# Microprocessor.net
KiCad netlist of a schematic drawn in Altium Designer
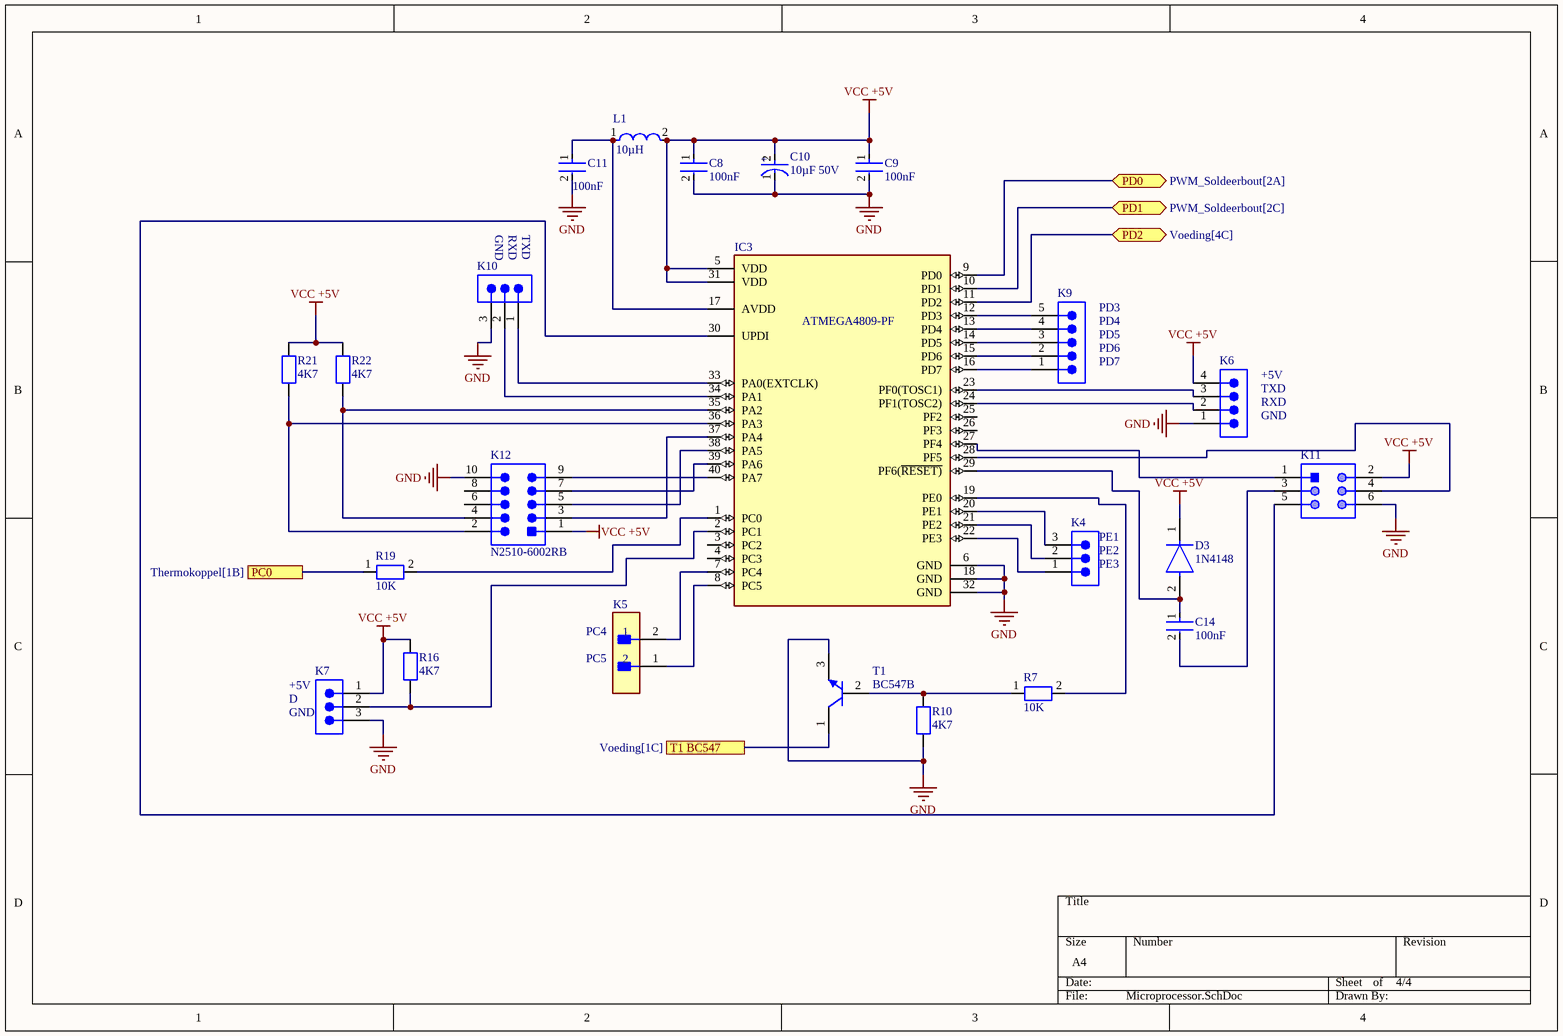
[diagram p0: Microprocessor.SchDoc]

(export (version "E")
  (design (tool "Eeschema 10.0.6"))
  (components
    (comp (ref "C8")
      (value "100nF")
      (footprint "FP-C0805C-DN-IPC_A")
      (description "Chip Multilayer Ceramic Capacitors for Automotive, 0805, 0.10uF, X7R, 15%, 10%, 50V, Grade 1")
      (fields (field (name "TOLERANCE") "10%"))
      (libsource (lib "soldeerstation") (part "cap 50V 100nF"))
    )
    (comp (ref "C9")
      (value "100nF")
      (footprint "FP-C0805C-DN-IPC_A")
      (description "Chip Multilayer Ceramic Capacitors for Automotive, 0805, 0.10uF, X7R, 15%, 10%, 50V, Grade 1")
      (fields (field (name "TOLERANCE") "10%"))
      (libsource (lib "soldeerstation") (part "cap 50V 100nF"))
    )
    (comp (ref "C10")
      (value "10µF 50V")
      (footprint "cap 10µF 50V")
      (description "Aluminum Electrolytic Capacitors (Radial Lead Type) 10uF ±20% 50V")
      (fields (field (name "TOLERANCE") "20%") (field (name "VOLTAGE") "50V"))
      (libsource (lib "soldeerstation") (part "10µF 50V"))
    )
    (comp (ref "C11")
      (value "100nF")
      (footprint "FP-C0805C-DN-IPC_A")
      (description "Chip Multilayer Ceramic Capacitors for Automotive, 0805, 0.10uF, X7R, 15%, 10%, 50V, Grade 1")
      (fields (field (name "TOLERANCE") "10%"))
      (libsource (lib "soldeerstation") (part "cap 50V 100nF"))
    )
    (comp (ref "C14")
      (value "100nF")
      (footprint "FP-C0805C-DN-IPC_A")
      (description "Chip Multilayer Ceramic Capacitors for Automotive, 0805, 0.10uF, X7R, 15%, 10%, 50V, Grade 1")
      (fields (field (name "TOLERANCE") "10%"))
      (libsource (lib "soldeerstation") (part "cap 50V 100nF"))
    )
    (comp (ref "D3")
      (value "1N4148")
      (footprint "1N4148")
      (description "DIODE GEN PURP 100V 200MA DO35")
      (fields (field (name "VOLTAGE") "100V"))
      (libsource (lib "soldeerstation") (part "1N4148"))
    )
    (comp (ref "IC3")
      (value "ATMEGA4809-PF")
      (footprint "ATMEGCPU")
      (description "IC MCU 8BIT 48KB FLASH 40DIP")
      (libsource (lib "soldeerstation") (part "ATMEGA4809-PF"))
    )
    (comp (ref "K4")
      (value "~")
      (footprint "Pinheader (1rij-3pin)")
      (description "0.025\" SQ Post Header, Through-hole, Vertical, -55 to 105 degC, 2.54 mm Pitch, 3-Pin, Male, RoHS")
      (fields (field (name "PARTNUMBER") "TSW-103-07-T-S") (field (name "MANUFACTURER") "Samtec"))
      (libsource (lib "soldeerstation") (part "Pinheader (1rij-3pin)"))
    )
    (comp (ref "K5")
      (value "~")
      (footprint "Pinheader (1rij-2pin)")
      (description "CONN HEADER VERT 2POS 2.54MM")
      (fields
        (field (name "OCTOPART") "https://octopart.com/m20-9990246-harwin-2590635")
        (field (name "MANUFACTURER") "Harwin")
      )
      (libsource (lib "soldeerstation") (part "Pinheader (1rij-2pin)"))
    )
    (comp (ref "K6")
      (value "~")
      (footprint "Pinheader (1rij-4pin)")
      (description "0.025\" SQ Post Header, Through-hole, Vertical, -55 to 125 degC, 2.54 mm Pitch, 4-Pin, Male, RoHS")
      (fields (field (name "PARTNUMBER") "TSW-104-08-L-S") (field (name "MANUFACTURER") "Samtec"))
      (libsource (lib "soldeerstation") (part "Pinheader (1rij - 4pin)"))
    )
    (comp (ref "K7")
      (value "~")
      (footprint "Pinheader (1rij-3pin)")
      (description "0.025\" SQ Post Header, Through-hole, Vertical, -55 to 105 degC, 2.54 mm Pitch, 3-Pin, Male, RoHS")
      (fields (field (name "PARTNUMBER") "TSW-103-07-T-S") (field (name "MANUFACTURER") "Samtec"))
      (libsource (lib "soldeerstation") (part "Pinheader (1rij-3pin)"))
    )
    (comp (ref "K9")
      (value "~")
      (footprint "Pinheader (1rij-5pin)")
      (description "0.025\" SQ Post Header, Through-hole, Vertical, -55 to 125 degC, 2.54 mm Pitch, 5-Pin, Male, RoHS")
      (fields (field (name "PARTNUMBER") "TSW-105-05-F-S") (field (name "MANUFACTURER") "Samtec"))
      (libsource (lib "soldeerstation") (part "Pinheader (1rij-5pin)"))
    )
    (comp (ref "K10")
      (value "~")
      (footprint "Pinheader (1rij-3pin)")
      (description "0.025\" SQ Post Header, Through-hole, Vertical, -55 to 105 degC, 2.54 mm Pitch, 3-Pin, Male, RoHS")
      (fields (field (name "PARTNUMBER") "TSW-103-07-T-S") (field (name "MANUFACTURER") "Samtec"))
      (libsource (lib "soldeerstation") (part "Pinheader (1rij-3pin)"))
    )
    (comp (ref "K11")
      (value "~")
      (footprint "Pinheader (2rij-6pin)")
      (description "THT Vertical Pin Header WR-PHD, Pitch 2.54 mm, Dual Row, 6 pins")
      (fields
        (field (name "MANUFACTURER") "Wurth Elektronik")
        (field (name "PART NUMBER") "61300621121")
        (field (name "PUBLISHER") "WurthElektronik")
      )
      (libsource (lib "soldeerstation") (part "Pinheader (2rij-6pin)"))
    )
    (comp (ref "K12")
      (value "N2510-6002RB")
      (footprint "boxheader")
      (fields (field (name "PARTNUMBER") "N2510") (field (name "MANUFACTURER") "3M"))
      (libsource (lib "soldeerstation") (part "boxheader"))
    )
    (comp (ref "L1")
      (value "10µH")
      (footprint "Spoel L1 10µH,130mA")
      (description "IR-2 10 10% B08")
      (fields (field (name "TOLERANCE") "10%") (field (name "OBSOLETE PART") "true"))
      (libsource (lib "soldeerstation") (part "Spoel L1 10µH,130mA"))
    )
    (comp (ref "R7")
      (value "10K")
      (footprint "Weerstand 1M ohm")
      (description "RES Thick Film, 10kΩ, 1%, 0.125W, 100ppm/°C, 0805")
      (fields (field (name "TOLERANCE") "1%"))
      (libsource (lib "soldeerstation") (part "Weerstand 10K ohm"))
    )
    (comp (ref "R10")
      (value "4K7")
      (footprint "Weerstand 1M ohm")
      (fields (field (name "MANUFACTURER") "Vishay Dale") (field (name "PART NUMBER") "CRCW08054K70JNEB"))
      (libsource (lib "soldeerstation") (part "Weerstand 4K7 ohm"))
    )
    (comp (ref "R16")
      (value "4K7")
      (footprint "Weerstand 1M ohm")
      (fields (field (name "MANUFACTURER") "Vishay Dale") (field (name "PART NUMBER") "CRCW08054K70JNEB"))
      (libsource (lib "soldeerstation") (part "Weerstand 4K7 ohm"))
    )
    (comp (ref "R19")
      (value "10K")
      (footprint "Weerstand 1M ohm")
      (description "RES Thick Film, 10kΩ, 1%, 0.125W, 100ppm/°C, 0805")
      (fields (field (name "TOLERANCE") "1%"))
      (libsource (lib "soldeerstation") (part "Weerstand 10K ohm"))
    )
    (comp (ref "R21")
      (value "4K7")
      (footprint "Weerstand 1M ohm")
      (fields (field (name "MANUFACTURER") "Vishay Dale") (field (name "PART NUMBER") "CRCW08054K70JNEB"))
      (libsource (lib "soldeerstation") (part "Weerstand 4K7 ohm"))
    )
    (comp (ref "R22")
      (value "4K7")
      (footprint "Weerstand 1M ohm")
      (fields (field (name "MANUFACTURER") "Vishay Dale") (field (name "PART NUMBER") "CRCW08054K70JNEB"))
      (libsource (lib "soldeerstation") (part "Weerstand 4K7 ohm"))
    )
    (comp (ref "T1")
      (value "BC547B")
      (footprint "sot23")
      (description "Amplifier Transistor, NPN Silicon, 3-Pin TO-92, Bulk Box")
      (fields (field (name "MANUFACTURER") "On Semiconductor"))
      (libsource (lib "soldeerstation") (part "sot23 (bc547)"))
    )
  )
  (nets
    (net (code "1") (name "/PC0") (class "Default")
      (node (ref "R19") (pin "1") (pinfunction "1_1") (pintype "passive"))
    )
    (net (code "2") (name "/PD0") (class "Default")
      (node (ref "IC3") (pin "9") (pinfunction "PD0_9") (pintype "bidirectional"))
    )
    (net (code "3") (name "/PD1") (class "Default")
      (node (ref "IC3") (pin "10") (pinfunction "PD1_10") (pintype "bidirectional"))
    )
    (net (code "4") (name "/PD2") (class "Default")
      (node (ref "IC3") (pin "11") (pinfunction "PD2_11") (pintype "bidirectional"))
    )
    (net (code "5") (name "/T1 BC547") (class "Default")
      (node (ref "T1") (pin "1") (pinfunction "C_1") (pintype "passive"))
    )
    (net (code "6") (name "GND") (class "Default")
      (node (ref "C10") (pin "1") (pinfunction "C_1") (pintype "passive"))
      (node (ref "C11") (pin "2") (pinfunction "2_2") (pintype "passive"))
      (node (ref "C8") (pin "2") (pinfunction "2_2") (pintype "passive"))
      (node (ref "C9") (pin "2") (pinfunction "2_2") (pintype "passive"))
      (node (ref "IC3") (pin "18") (pinfunction "GND_18") (pintype "power_in"))
      (node (ref "IC3") (pin "32") (pinfunction "GND_32") (pintype "power_in"))
      (node (ref "IC3") (pin "6") (pinfunction "GND_6") (pintype "power_in"))
      (node (ref "K10") (pin "3") (pinfunction "3_3") (pintype "passive"))
      (node (ref "K11") (pin "6") (pinfunction "6_6") (pintype "passive"))
      (node (ref "K12") (pin "10") (pinfunction "10_10") (pintype "passive"))
      (node (ref "K6") (pin "1") (pinfunction "1_1") (pintype "passive"))
      (node (ref "K7") (pin "3") (pinfunction "3_3") (pintype "passive"))
      (node (ref "R10") (pin "1") (pinfunction "1_1") (pintype "passive"))
      (node (ref "T1") (pin "3") (pinfunction "E_3") (pintype "passive"))
    )
    (net (code "7") (name "Net-(C14-Pad2)") (class "Default")
      (node (ref "C14") (pin "2") (pinfunction "2_2") (pintype "passive"))
      (node (ref "K11") (pin "3") (pinfunction "3_3") (pintype "passive"))
    )
    (net (code "8") (name "Net-(D3-A)") (class "Default")
      (node (ref "C14") (pin "1") (pinfunction "1_1") (pintype "passive"))
      (node (ref "D3") (pin "2") (pinfunction "A_2") (pintype "passive"))
      (node (ref "IC3") (pin "29") (pinfunction "PF6(~{RESET)}_29") (pintype "bidirectional"))
    )
    (net (code "9") (name "Net-(IC3-AVDD)") (class "Default")
      (node (ref "C11") (pin "1") (pinfunction "1_1") (pintype "passive"))
      (node (ref "IC3") (pin "17") (pinfunction "AVDD_17") (pintype "power_in"))
      (node (ref "L1") (pin "1") (pinfunction "1_1") (pintype "passive"))
    )
    (net (code "10") (name "Net-(IC3-PA0(EXTCLK))") (class "Default")
      (node (ref "IC3") (pin "33") (pinfunction "PA0(EXTCLK)_33") (pintype "bidirectional"))
      (node (ref "K10") (pin "1") (pinfunction "1_1") (pintype "passive"))
    )
    (net (code "11") (name "Net-(IC3-PA1)") (class "Default")
      (node (ref "IC3") (pin "34") (pinfunction "PA1_34") (pintype "bidirectional"))
      (node (ref "K10") (pin "2") (pinfunction "2_2") (pintype "passive"))
    )
    (net (code "12") (name "Net-(IC3-PA2)") (class "Default")
      (node (ref "IC3") (pin "35") (pinfunction "PA2_35") (pintype "bidirectional"))
      (node (ref "K12") (pin "4") (pinfunction "4_4") (pintype "passive"))
      (node (ref "R22") (pin "1") (pinfunction "1_1") (pintype "passive"))
    )
    (net (code "13") (name "Net-(IC3-PA3)") (class "Default")
      (node (ref "IC3") (pin "36") (pinfunction "PA3_36") (pintype "bidirectional"))
      (node (ref "K12") (pin "2") (pinfunction "2_2") (pintype "passive"))
      (node (ref "R21") (pin "1") (pinfunction "1_1") (pintype "passive"))
    )
    (net (code "14") (name "Net-(IC3-PA4)") (class "Default")
      (node (ref "IC3") (pin "37") (pinfunction "PA4_37") (pintype "bidirectional"))
      (node (ref "K12") (pin "3") (pinfunction "3_3") (pintype "passive"))
    )
    (net (code "15") (name "Net-(IC3-PA5)") (class "Default")
      (node (ref "IC3") (pin "38") (pinfunction "PA5_38") (pintype "bidirectional"))
      (node (ref "K12") (pin "5") (pinfunction "5_5") (pintype "passive"))
    )
    (net (code "16") (name "Net-(IC3-PA6)") (class "Default")
      (node (ref "IC3") (pin "39") (pinfunction "PA6_39") (pintype "bidirectional"))
      (node (ref "K12") (pin "7") (pinfunction "7_7") (pintype "passive"))
    )
    (net (code "17") (name "Net-(IC3-PA7)") (class "Default")
      (node (ref "IC3") (pin "40") (pinfunction "PA7_40") (pintype "bidirectional"))
      (node (ref "K12") (pin "9") (pinfunction "9_9") (pintype "passive"))
    )
    (net (code "18") (name "Net-(IC3-PC0)") (class "Default")
      (node (ref "IC3") (pin "1") (pinfunction "PC0_1") (pintype "bidirectional"))
      (node (ref "R19") (pin "2") (pinfunction "2_2") (pintype "passive"))
    )
    (net (code "19") (name "Net-(IC3-PC1)") (class "Default")
      (node (ref "IC3") (pin "2") (pinfunction "PC1_2") (pintype "bidirectional"))
      (node (ref "K7") (pin "2") (pinfunction "2_2") (pintype "passive"))
      (node (ref "R16") (pin "1") (pinfunction "1_1") (pintype "passive"))
    )
    (net (code "20") (name "Net-(IC3-PC4)") (class "Default")
      (node (ref "IC3") (pin "7") (pinfunction "PC4_7") (pintype "bidirectional"))
      (node (ref "K5") (pin "2") (pinfunction "2_2") (pintype "passive"))
    )
    (net (code "21") (name "Net-(IC3-PC5)") (class "Default")
      (node (ref "IC3") (pin "8") (pinfunction "PC5_8") (pintype "bidirectional"))
      (node (ref "K5") (pin "1") (pinfunction "1_1") (pintype "passive"))
    )
    (net (code "22") (name "Net-(IC3-PD3)") (class "Default")
      (node (ref "IC3") (pin "12") (pinfunction "PD3_12") (pintype "bidirectional"))
      (node (ref "K9") (pin "5") (pinfunction "5_5") (pintype "passive"))
    )
    (net (code "23") (name "Net-(IC3-PD4)") (class "Default")
      (node (ref "IC3") (pin "13") (pinfunction "PD4_13") (pintype "bidirectional"))
      (node (ref "K9") (pin "4") (pinfunction "4_4") (pintype "passive"))
    )
    (net (code "24") (name "Net-(IC3-PD5)") (class "Default")
      (node (ref "IC3") (pin "14") (pinfunction "PD5_14") (pintype "bidirectional"))
      (node (ref "K9") (pin "3") (pinfunction "3_3") (pintype "passive"))
    )
    (net (code "25") (name "Net-(IC3-PD6)") (class "Default")
      (node (ref "IC3") (pin "15") (pinfunction "PD6_15") (pintype "bidirectional"))
      (node (ref "K9") (pin "2") (pinfunction "2_2") (pintype "passive"))
    )
    (net (code "26") (name "Net-(IC3-PD7)") (class "Default")
      (node (ref "IC3") (pin "16") (pinfunction "PD7_16") (pintype "bidirectional"))
      (node (ref "K9") (pin "1") (pinfunction "1_1") (pintype "passive"))
    )
    (net (code "27") (name "Net-(IC3-PE0)") (class "Default")
      (node (ref "IC3") (pin "19") (pinfunction "PE0_19") (pintype "bidirectional"))
      (node (ref "R7") (pin "2") (pinfunction "2_2") (pintype "passive"))
    )
    (net (code "28") (name "Net-(IC3-PE1)") (class "Default")
      (node (ref "IC3") (pin "20") (pinfunction "PE1_20") (pintype "bidirectional"))
      (node (ref "K4") (pin "3") (pinfunction "3_3") (pintype "passive"))
    )
    (net (code "29") (name "Net-(IC3-PE2)") (class "Default")
      (node (ref "IC3") (pin "21") (pinfunction "PE2_21") (pintype "bidirectional"))
      (node (ref "K4") (pin "2") (pinfunction "2_2") (pintype "passive"))
    )
    (net (code "30") (name "Net-(IC3-PE3)") (class "Default")
      (node (ref "IC3") (pin "22") (pinfunction "PE3_22") (pintype "bidirectional"))
      (node (ref "K4") (pin "1") (pinfunction "1_1") (pintype "passive"))
    )
    (net (code "31") (name "Net-(IC3-PF0(TOSC1))") (class "Default")
      (node (ref "IC3") (pin "23") (pinfunction "PF0(TOSC1)_23") (pintype "bidirectional"))
      (node (ref "K6") (pin "3") (pinfunction "3_3") (pintype "passive"))
    )
    (net (code "32") (name "Net-(IC3-PF1(TOSC2))") (class "Default")
      (node (ref "IC3") (pin "24") (pinfunction "PF1(TOSC2)_24") (pintype "bidirectional"))
      (node (ref "K6") (pin "2") (pinfunction "2_2") (pintype "passive"))
    )
    (net (code "33") (name "Net-(IC3-PF4)") (class "Default")
      (node (ref "IC3") (pin "27") (pinfunction "PF4_27") (pintype "bidirectional"))
      (node (ref "K11") (pin "1") (pinfunction "1_1") (pintype "passive"))
    )
    (net (code "34") (name "Net-(IC3-PF5)") (class "Default")
      (node (ref "IC3") (pin "28") (pinfunction "PF5_28") (pintype "bidirectional"))
      (node (ref "K11") (pin "4") (pinfunction "4_4") (pintype "passive"))
    )
    (net (code "35") (name "Net-(IC3-UPDI)") (class "Default")
      (node (ref "IC3") (pin "30") (pinfunction "UPDI_30") (pintype "passive"))
      (node (ref "K11") (pin "5") (pinfunction "5_5") (pintype "passive"))
    )
    (net (code "36") (name "Net-(T1-B)") (class "Default")
      (node (ref "R10") (pin "2") (pinfunction "2_2") (pintype "passive"))
      (node (ref "R7") (pin "1") (pinfunction "1_1") (pintype "passive"))
      (node (ref "T1") (pin "2") (pinfunction "B_2") (pintype "passive"))
    )
    (net (code "37") (name "VCC +5V") (class "Default")
      (node (ref "C10") (pin "2") (pinfunction "A_2") (pintype "passive"))
      (node (ref "C8") (pin "1") (pinfunction "1_1") (pintype "passive"))
      (node (ref "C9") (pin "1") (pinfunction "1_1") (pintype "passive"))
      (node (ref "D3") (pin "1") (pinfunction "C_1") (pintype "passive"))
      (node (ref "IC3") (pin "31") (pinfunction "VDD_31") (pintype "power_in"))
      (node (ref "IC3") (pin "5") (pinfunction "VDD_5") (pintype "power_in"))
      (node (ref "K11") (pin "2") (pinfunction "2_2") (pintype "passive"))
      (node (ref "K12") (pin "1") (pinfunction "1_1") (pintype "passive"))
      (node (ref "K6") (pin "4") (pinfunction "4_4") (pintype "passive"))
      (node (ref "K7") (pin "1") (pinfunction "1_1") (pintype "passive"))
      (node (ref "L1") (pin "2") (pinfunction "2_2") (pintype "passive"))
      (node (ref "R16") (pin "2") (pinfunction "2_2") (pintype "passive"))
      (node (ref "R21") (pin "2") (pinfunction "2_2") (pintype "passive"))
      (node (ref "R22") (pin "2") (pinfunction "2_2") (pintype "passive"))
    )
    (net (code "38") (name "unconnected-(IC3-PC2-Pad3)") (class "Default")
      (node (ref "IC3") (pin "3") (pinfunction "PC2_3") (pintype "bidirectional"))
    )
    (net (code "39") (name "unconnected-(IC3-PC3-Pad4)") (class "Default")
      (node (ref "IC3") (pin "4") (pinfunction "PC3_4") (pintype "bidirectional"))
    )
    (net (code "40") (name "unconnected-(IC3-PF2-Pad25)") (class "Default")
      (node (ref "IC3") (pin "25") (pinfunction "PF2_25") (pintype "bidirectional"))
    )
    (net (code "41") (name "unconnected-(IC3-PF3-Pad26)") (class "Default")
      (node (ref "IC3") (pin "26") (pinfunction "PF3_26") (pintype "bidirectional"))
    )
    (net (code "42") (name "unconnected-(K12-Pad6)") (class "Default")
      (node (ref "K12") (pin "6") (pinfunction "6_6") (pintype "passive"))
    )
    (net (code "43") (name "unconnected-(K12-Pad8)") (class "Default")
      (node (ref "K12") (pin "8") (pinfunction "8_8") (pintype "passive"))
    )
  )
)
